# houz_dmxSlave.net
KiCad netlist of a schematic drawn in EAGLE
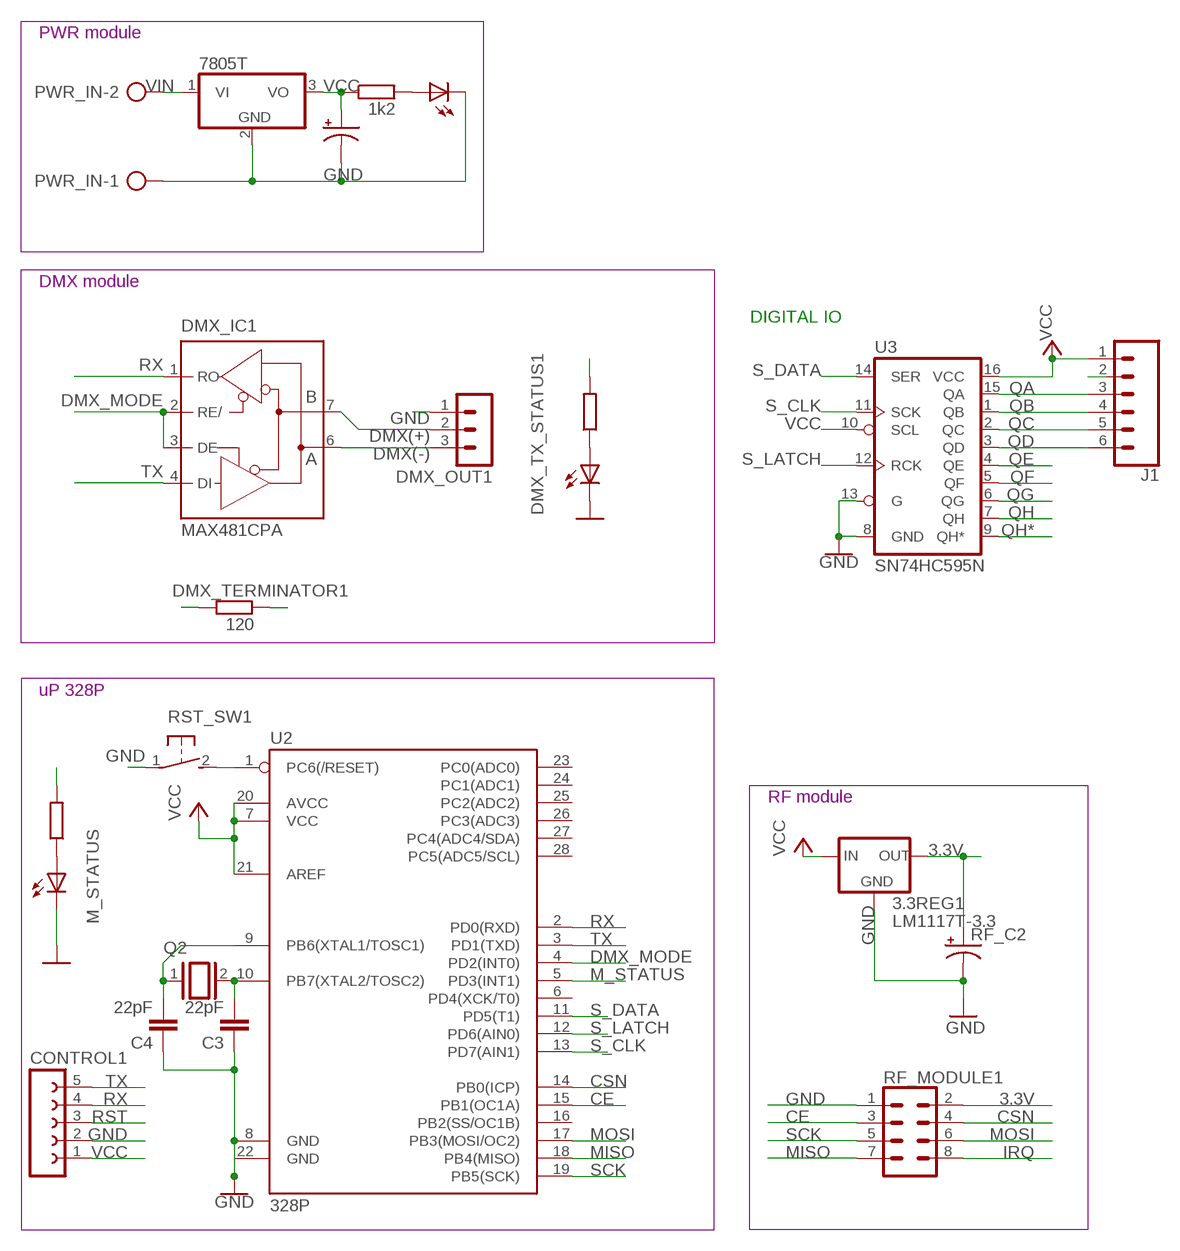
[diagram p0: schematic, sheet 1]

(export (version "E")
  (design (tool "Eeschema 10.0.6"))
  (components
    (comp (ref "3.3REG1")
      (value "LM1117T-3.3")
      (footprint "eagle-import:TO220")
      (libsource (lib "eagle-import") (part "LM1117T-3.3"))
    )
    (comp (ref "C3")
      (value "22pF")
      (footprint "eagle-import:C050-030X075")
      (libsource (lib "eagle-import") (part "C-EU050-030X075"))
    )
    (comp (ref "C4")
      (value "22pF")
      (footprint "eagle-import:C050-030X075")
      (libsource (lib "eagle-import") (part "C-EU050-030X075"))
    )
    (comp (ref "CONTROL1")
      (value "FE05-1")
      (footprint "eagle-import:FE05-1")
      (libsource (lib "eagle-import") (part "FE05-1"))
    )
    (comp (ref "DMX_IC1")
      (value "MAX481CPA")
      (footprint "eagle-import:DIL08")
      (fields (field (name "MPN") "MAX481CPA+"))
      (libsource (lib "eagle-import") (part "MAX481CPA"))
    )
    (comp (ref "DMX_OUT1")
      (value "MA03-1")
      (footprint "eagle-import:MA03-1")
      (libsource (lib "eagle-import") (part "MA03-1"))
    )
    (comp (ref "DMX_R1")
      (value "R-EU_0204/5")
      (footprint "eagle-import:0204_5")
      (libsource (lib "eagle-import") (part "R-EU_0204/5"))
    )
    (comp (ref "DMX_TERMINATOR1")
      (value "120")
      (footprint "eagle-import:0204_5")
      (libsource (lib "eagle-import") (part "R-EU_0204/5"))
    )
    (comp (ref "DMX_TX_STATUS1")
      (value "LED3MM")
      (footprint "eagle-import:LED3MM")
      (libsource (lib "eagle-import") (part "LED3MM"))
    )
    (comp (ref "J1")
      (value "CONN_06NO_SILK_FEMALE_PTH")
      (footprint "eagle-import:1X06_NO_SILK")
      (libsource (lib "eagle-import") (part "CONN_06NO_SILK_FEMALE_PTH"))
    )
    (comp (ref "M_STATUS")
      (value "LED3MM")
      (footprint "eagle-import:LED3MM")
      (libsource (lib "eagle-import") (part "LED3MM"))
    )
    (comp (ref "M_STATUS_R1")
      (value "R-EU_0207/10")
      (footprint "eagle-import:0207_10")
      (libsource (lib "eagle-import") (part "R-EU_0207/10"))
    )
    (comp (ref "PWR_C1")
      (value "CPOL-USE5-10.5")
      (footprint "eagle-import:E5-10,5")
      (libsource (lib "eagle-import") (part "CPOL-USE5-10.5"))
    )
    (comp (ref "PWR_IC1")
      (value "7805T")
      (footprint "eagle-import:TO220H")
      (libsource (lib "eagle-import") (part "78T05"))
    )
    (comp (ref "PWR_IN")
      (value "AK500/2-H")
      (footprint "eagle-import:AK500_2-H")
      (libsource (lib "eagle-import") (part "AK500/2-H"))
    )
    (comp (ref "PWR_L1")
      (value "LED3MM")
      (footprint "eagle-import:LED3MM")
      (libsource (lib "eagle-import") (part "LED3MM"))
    )
    (comp (ref "PWR_R1")
      (value "1k2")
      (footprint "eagle-import:0204_5")
      (libsource (lib "eagle-import") (part "R-EU_0204/5"))
    )
    (comp (ref "Q2")
      (value "16MHz")
      (footprint "eagle-import:QS")
      (libsource (lib "eagle-import") (part "XTAL/S"))
    )
    (comp (ref "RF_C2")
      (value "CPOL-USE5-10.5")
      (footprint "eagle-import:E5-10,5")
      (libsource (lib "eagle-import") (part "CPOL-USE5-10.5"))
    )
    (comp (ref "RF_MODULE1")
      (value "CONN_04X2")
      (footprint "eagle-import:2X4")
      (libsource (lib "eagle-import") (part "CONN_04X2"))
    )
    (comp (ref "RST_SW1")
      (value "DTS-3")
      (footprint "eagle-import:DTS-3")
      (libsource (lib "eagle-import") (part "DTS-3"))
    )
    (comp (ref "U2")
      (value "328P")
      (footprint "eagle-import:DIP28")
      (libsource (lib "eagle-import") (part "ATMEGA328P_PDIP"))
    )
    (comp (ref "U3")
      (value "SN74HC595N")
      (footprint "eagle-import:DIP16")
      (libsource (lib "eagle-import") (part "74595NHC"))
    )
  )
  (nets
    (net (code "1") (name "/3.3V") (class "Default")
      (node (ref "3.3REG1") (pin "2") (pinfunction "OUT_2") (pintype "passive"))
      (node (ref "RF_C2") (pin "+") (pinfunction "+_+") (pintype "passive"))
      (node (ref "RF_MODULE1") (pin "2") (pinfunction "2_2") (pintype "passive"))
    )
    (net (code "2") (name "/CE") (class "Default")
      (node (ref "RF_MODULE1") (pin "3") (pinfunction "3_3") (pintype "passive"))
      (node (ref "U2") (pin "15") (pinfunction "PB1(OC1A)_15") (pintype "bidirectional"))
    )
    (net (code "3") (name "/CSN") (class "Default")
      (node (ref "RF_MODULE1") (pin "4") (pinfunction "4_4") (pintype "passive"))
      (node (ref "U2") (pin "14") (pinfunction "PB0(ICP)_14") (pintype "bidirectional"))
    )
    (net (code "4") (name "/DMX(+)") (class "Default")
      (node (ref "DMX_IC1") (pin "7") (pinfunction "B_7") (pintype "passive"))
      (node (ref "DMX_OUT1") (pin "2") (pinfunction "2_2") (pintype "passive"))
      (node (ref "DMX_R1") (pin "2") (pinfunction "2_2") (pintype "passive"))
      (node (ref "DMX_TERMINATOR1") (pin "2") (pinfunction "2_2") (pintype "passive"))
    )
    (net (code "5") (name "/DMX(-)") (class "Default")
      (node (ref "DMX_IC1") (pin "6") (pinfunction "A_6") (pintype "passive"))
      (node (ref "DMX_OUT1") (pin "3") (pinfunction "3_3") (pintype "passive"))
      (node (ref "DMX_TERMINATOR1") (pin "1") (pinfunction "1_1") (pintype "passive"))
    )
    (net (code "6") (name "/DMX_MODE") (class "Default")
      (node (ref "DMX_IC1") (pin "2") (pinfunction "RE/_2") (pintype "input"))
      (node (ref "DMX_IC1") (pin "3") (pinfunction "DE_3") (pintype "input"))
      (node (ref "U2") (pin "4") (pinfunction "PD2(INT0)_4") (pintype "bidirectional"))
    )
    (net (code "7") (name "/IRQ") (class "Default")
      (node (ref "RF_MODULE1") (pin "8") (pinfunction "8_8") (pintype "passive"))
    )
    (net (code "8") (name "/MISO") (class "Default")
      (node (ref "RF_MODULE1") (pin "7") (pinfunction "7_7") (pintype "passive"))
      (node (ref "U2") (pin "18") (pinfunction "PB4(MISO)_18") (pintype "bidirectional"))
    )
    (net (code "9") (name "/MOSI") (class "Default")
      (node (ref "RF_MODULE1") (pin "6") (pinfunction "6_6") (pintype "passive"))
      (node (ref "U2") (pin "17") (pinfunction "PB3(MOSI/OC2)_17") (pintype "bidirectional"))
    )
    (net (code "10") (name "/M_STATUS") (class "Default")
      (node (ref "M_STATUS_R1") (pin "2") (pinfunction "2_2") (pintype "passive"))
      (node (ref "U2") (pin "5") (pinfunction "PD3(INT1)_5") (pintype "bidirectional"))
    )
    (net (code "11") (name "/QA") (class "Default")
      (node (ref "J1") (pin "3") (pinfunction "3_3") (pintype "passive"))
      (node (ref "U3") (pin "15") (pinfunction "QA_15") (pintype "tri_state"))
    )
    (net (code "12") (name "/QB") (class "Default")
      (node (ref "J1") (pin "4") (pinfunction "4_4") (pintype "passive"))
      (node (ref "U3") (pin "1") (pinfunction "QB_1") (pintype "tri_state"))
    )
    (net (code "13") (name "/QC") (class "Default")
      (node (ref "J1") (pin "5") (pinfunction "5_5") (pintype "passive"))
      (node (ref "U3") (pin "2") (pinfunction "QC_2") (pintype "tri_state"))
    )
    (net (code "14") (name "/QD") (class "Default")
      (node (ref "J1") (pin "6") (pinfunction "6_6") (pintype "passive"))
      (node (ref "U3") (pin "3") (pinfunction "QD_3") (pintype "tri_state"))
    )
    (net (code "15") (name "/QE") (class "Default")
      (node (ref "U3") (pin "4") (pinfunction "QE_4") (pintype "tri_state"))
    )
    (net (code "16") (name "/QF") (class "Default")
      (node (ref "U3") (pin "5") (pinfunction "QF_5") (pintype "tri_state"))
    )
    (net (code "17") (name "/QG") (class "Default")
      (node (ref "U3") (pin "6") (pinfunction "QG_6") (pintype "tri_state"))
    )
    (net (code "18") (name "/QH") (class "Default")
      (node (ref "U3") (pin "7") (pinfunction "QH_7") (pintype "tri_state"))
    )
    (net (code "19") (name "/QH*") (class "Default")
      (node (ref "U3") (pin "9") (pinfunction "QH*_9") (pintype "tri_state"))
    )
    (net (code "20") (name "/RST") (class "Default")
      (node (ref "CONTROL1") (pin "3") (pinfunction "3_3") (pintype "passive"))
      (node (ref "RST_SW1") (pin "2") (pinfunction "2_2") (pintype "passive"))
      (node (ref "U2") (pin "1") (pinfunction "PC6(/RESET)_1") (pintype "bidirectional"))
    )
    (net (code "21") (name "/RX") (class "Default")
      (node (ref "CONTROL1") (pin "4") (pinfunction "4_4") (pintype "passive"))
      (node (ref "DMX_IC1") (pin "1") (pinfunction "RO_1") (pintype "output"))
      (node (ref "U2") (pin "2") (pinfunction "PD0(RXD)_2") (pintype "bidirectional"))
    )
    (net (code "22") (name "/SCK") (class "Default")
      (node (ref "RF_MODULE1") (pin "5") (pinfunction "5_5") (pintype "passive"))
      (node (ref "U2") (pin "19") (pinfunction "PB5(SCK)_19") (pintype "bidirectional"))
    )
    (net (code "23") (name "/S_CLK") (class "Default")
      (node (ref "U2") (pin "13") (pinfunction "PD7(AIN1)_13") (pintype "bidirectional"))
      (node (ref "U3") (pin "11") (pinfunction "SCK_11") (pintype "input"))
    )
    (net (code "24") (name "/S_DATA") (class "Default")
      (node (ref "U2") (pin "11") (pinfunction "PD5(T1)_11") (pintype "bidirectional"))
      (node (ref "U3") (pin "14") (pinfunction "SER_14") (pintype "input"))
    )
    (net (code "25") (name "/S_LATCH") (class "Default")
      (node (ref "U2") (pin "12") (pinfunction "PD6(AIN0)_12") (pintype "bidirectional"))
      (node (ref "U3") (pin "12") (pinfunction "RCK_12") (pintype "input"))
    )
    (net (code "26") (name "/TX") (class "Default")
      (node (ref "CONTROL1") (pin "5") (pinfunction "5_5") (pintype "passive"))
      (node (ref "DMX_IC1") (pin "4") (pinfunction "DI_4") (pintype "input"))
      (node (ref "U2") (pin "3") (pinfunction "PD1(TXD)_3") (pintype "bidirectional"))
    )
    (net (code "27") (name "/VIN") (class "Default")
      (node (ref "PWR_IC1") (pin "1") (pinfunction "VI_1") (pintype "input"))
      (node (ref "PWR_IN") (pin "2") (pinfunction "KL_2") (pintype "passive"))
    )
    (net (code "28") (name "GND") (class "Default")
      (node (ref "3.3REG1") (pin "1") (pinfunction "GND_1") (pintype "input"))
      (node (ref "C3") (pin "1") (pinfunction "1_1") (pintype "passive"))
      (node (ref "C4") (pin "1") (pinfunction "1_1") (pintype "passive"))
      (node (ref "CONTROL1") (pin "2") (pinfunction "2_2") (pintype "passive"))
      (node (ref "DMX_OUT1") (pin "1") (pinfunction "1_1") (pintype "passive"))
      (node (ref "DMX_TX_STATUS1") (pin "K") (pinfunction "C_K") (pintype "passive"))
      (node (ref "J1") (pin "2") (pinfunction "2_2") (pintype "passive"))
      (node (ref "M_STATUS") (pin "K") (pinfunction "C_K") (pintype "passive"))
      (node (ref "PWR_C1") (pin "-") (pinfunction "-_-") (pintype "passive"))
      (node (ref "PWR_IC1") (pin "2") (pinfunction "GND_2") (pintype "passive"))
      (node (ref "PWR_IN") (pin "1") (pinfunction "KL_1") (pintype "passive"))
      (node (ref "PWR_L1") (pin "K") (pinfunction "C_K") (pintype "passive"))
      (node (ref "RF_C2") (pin "-") (pinfunction "-_-") (pintype "passive"))
      (node (ref "RF_MODULE1") (pin "1") (pinfunction "1_1") (pintype "passive"))
      (node (ref "RST_SW1") (pin "1") (pinfunction "1_1") (pintype "passive"))
      (node (ref "U2") (pin "22") (pinfunction "GND_22") (pintype "bidirectional"))
      (node (ref "U2") (pin "8") (pinfunction "GND_8") (pintype "bidirectional"))
      (node (ref "U3") (pin "13") (pinfunction "G_13") (pintype "input"))
      (node (ref "U3") (pin "8") (pinfunction "GND_8") (pintype "power_in"))
    )
    (net (code "29") (name "Net-(DMX_R1-Pad1)") (class "Default")
      (node (ref "DMX_R1") (pin "1") (pinfunction "1_1") (pintype "passive"))
      (node (ref "DMX_TX_STATUS1") (pin "A") (pinfunction "A_A") (pintype "passive"))
    )
    (net (code "30") (name "Net-(M_STATUS-PadA)") (class "Default")
      (node (ref "M_STATUS") (pin "A") (pinfunction "A_A") (pintype "passive"))
      (node (ref "M_STATUS_R1") (pin "1") (pinfunction "1_1") (pintype "passive"))
    )
    (net (code "31") (name "Net-(PWR_L1-PadA)") (class "Default")
      (node (ref "PWR_L1") (pin "A") (pinfunction "A_A") (pintype "passive"))
      (node (ref "PWR_R1") (pin "2") (pinfunction "2_2") (pintype "passive"))
    )
    (net (code "32") (name "Net-(U2-PB6(XTAL1{slash}TOSC1))") (class "Default")
      (node (ref "C4") (pin "2") (pinfunction "2_2") (pintype "passive"))
      (node (ref "Q2") (pin "1") (pinfunction "1_1") (pintype "passive"))
      (node (ref "U2") (pin "9") (pinfunction "PB6(XTAL1/TOSC1)_9") (pintype "bidirectional"))
    )
    (net (code "33") (name "Net-(U2-PB7(XTAL2{slash}TOSC2))") (class "Default")
      (node (ref "C3") (pin "2") (pinfunction "2_2") (pintype "passive"))
      (node (ref "Q2") (pin "2") (pinfunction "2_2") (pintype "passive"))
      (node (ref "U2") (pin "10") (pinfunction "PB7(XTAL2/TOSC2)_10") (pintype "bidirectional"))
    )
    (net (code "34") (name "VCC") (class "Default")
      (node (ref "3.3REG1") (pin "3") (pinfunction "IN_3") (pintype "input"))
      (node (ref "CONTROL1") (pin "1") (pinfunction "1_1") (pintype "passive"))
      (node (ref "J1") (pin "1") (pinfunction "1_1") (pintype "passive"))
      (node (ref "PWR_C1") (pin "+") (pinfunction "+_+") (pintype "passive"))
      (node (ref "PWR_IC1") (pin "3") (pinfunction "VO_3") (pintype "passive"))
      (node (ref "PWR_R1") (pin "1") (pinfunction "1_1") (pintype "passive"))
      (node (ref "U2") (pin "20") (pinfunction "AVCC_20") (pintype "bidirectional"))
      (node (ref "U2") (pin "21") (pinfunction "AREF_21") (pintype "bidirectional"))
      (node (ref "U2") (pin "7") (pinfunction "VCC_7") (pintype "bidirectional"))
      (node (ref "U3") (pin "10") (pinfunction "SCL_10") (pintype "input"))
      (node (ref "U3") (pin "16") (pinfunction "VCC_16") (pintype "power_in"))
    )
    (net (code "35") (name "unconnected-(U2-PB2(SS{slash}OC1B)-Pad16)") (class "Default")
      (node (ref "U2") (pin "16") (pinfunction "PB2(SS/OC1B)_16") (pintype "bidirectional"))
    )
    (net (code "36") (name "unconnected-(U2-PC0(ADC0)-Pad23)") (class "Default")
      (node (ref "U2") (pin "23") (pinfunction "PC0(ADC0)_23") (pintype "bidirectional"))
    )
    (net (code "37") (name "unconnected-(U2-PC1(ADC1)-Pad24)") (class "Default")
      (node (ref "U2") (pin "24") (pinfunction "PC1(ADC1)_24") (pintype "bidirectional"))
    )
    (net (code "38") (name "unconnected-(U2-PC2(ADC2)-Pad25)") (class "Default")
      (node (ref "U2") (pin "25") (pinfunction "PC2(ADC2)_25") (pintype "bidirectional"))
    )
    (net (code "39") (name "unconnected-(U2-PC3(ADC3)-Pad26)") (class "Default")
      (node (ref "U2") (pin "26") (pinfunction "PC3(ADC3)_26") (pintype "bidirectional"))
    )
    (net (code "40") (name "unconnected-(U2-PC4(ADC4{slash}SDA)-Pad27)") (class "Default")
      (node (ref "U2") (pin "27") (pinfunction "PC4(ADC4/SDA)_27") (pintype "bidirectional"))
    )
    (net (code "41") (name "unconnected-(U2-PC5(ADC5{slash}SCL)-Pad28)") (class "Default")
      (node (ref "U2") (pin "28") (pinfunction "PC5(ADC5/SCL)_28") (pintype "bidirectional"))
    )
    (net (code "42") (name "unconnected-(U2-PD4(XCK{slash}T0)-Pad6)") (class "Default")
      (node (ref "U2") (pin "6") (pinfunction "PD4(XCK/T0)_6") (pintype "bidirectional"))
    )
  )
)
